# PowerBoard.net
KiCad netlist of a schematic drawn in Altium Designer
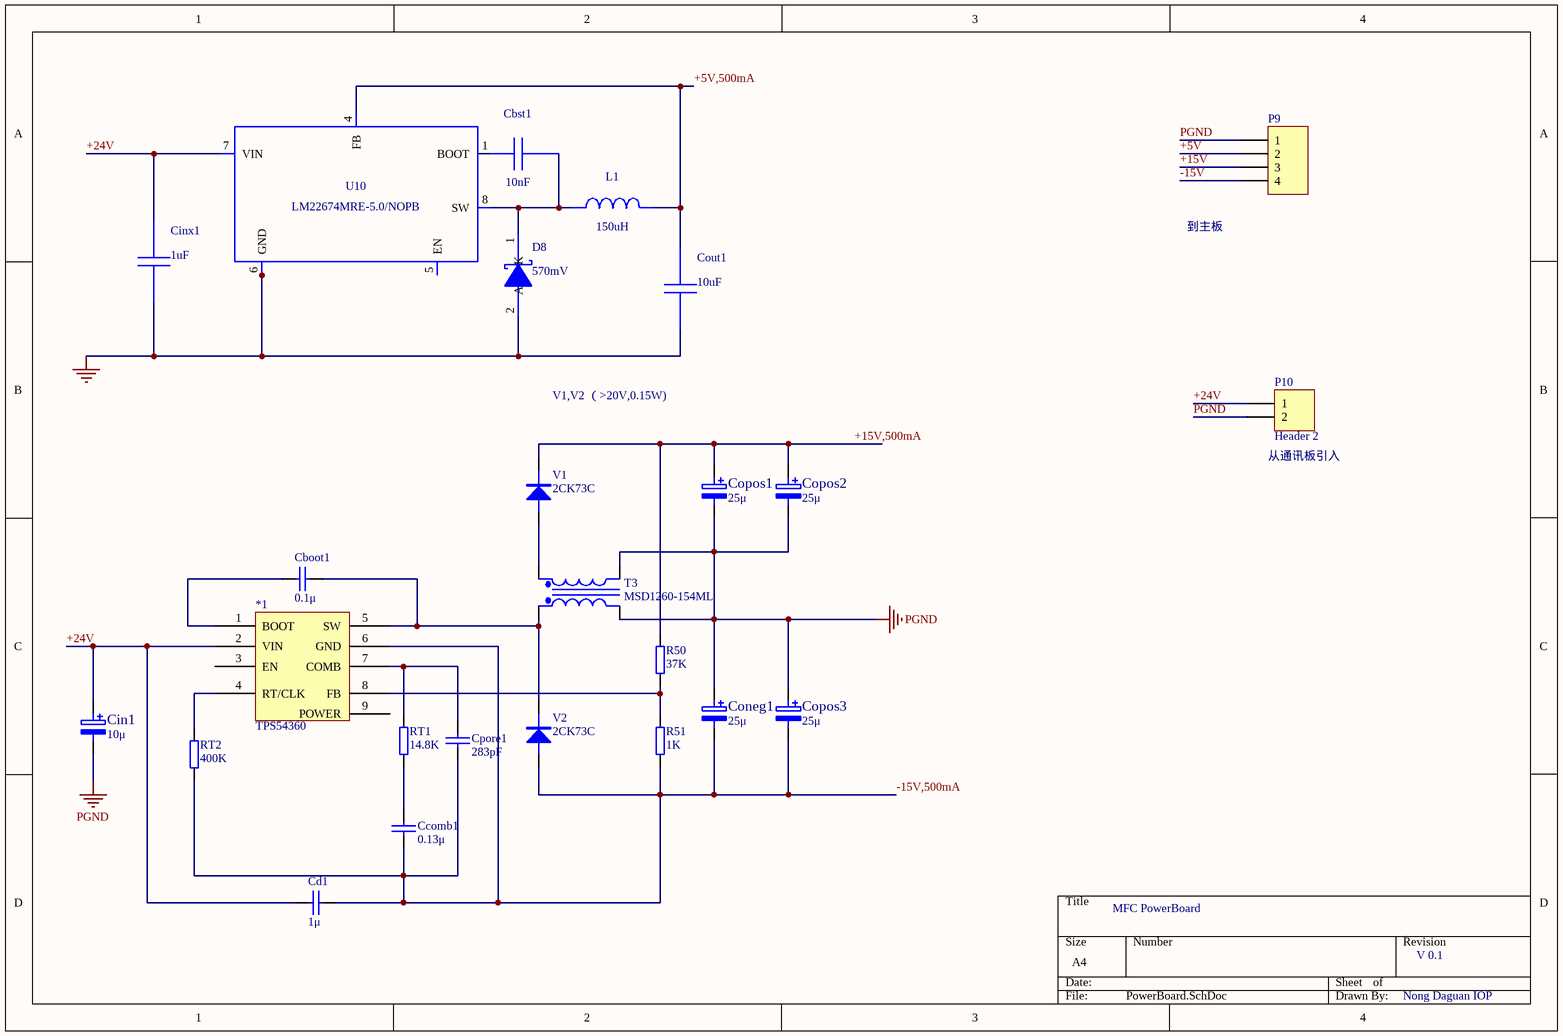
[diagram p0: PowerBoard.SchDoc]

(export (version "E")
  (design (tool "Eeschema 10.0.6"))
  (components
    (comp (ref "*1") (value "TPS54360") (libsource (lib "1.60") (part "TPS54360")))
    (comp (ref "Cboot1") (value "0.1μ") (footprint "C.1") (libsource (lib "1.60") (part "CAP")))
    (comp (ref "Cbst1")
      (value "10nF")
      (description "C0805C103K5RACTU")
      (libsource (lib "TI WEBENCH") (part "Cbst"))
    )
    (comp (ref "Ccomb1") (value "0.13μ") (footprint "C.1") (libsource (lib "1.60") (part "CAP")))
    (comp (ref "Cd1") (value "1μ") (footprint "C.1") (libsource (lib "1.60") (part "CAP")))
    (comp (ref "Cin1") (value "10μ") (footprint "CA-22U") (libsource (lib "1.60") (part "ELECTRO2")))
    (comp (ref "Cinx1")
      (value "1uF")
      (description "C1608X5R1H105K08")
      (fields (field (name "MANUFACTURER PART NUMBER") "C1608X5R1H105K080AB"))
      (libsource (lib "TI WEBENCH") (part "Cinx"))
    )
    (comp (ref "Coneg1") (value "25μ") (footprint "CA-22U") (libsource (lib "1.60") (part "ELECTRO2")))
    (comp (ref "Copos1") (value "25μ") (footprint "CA-22U") (libsource (lib "1.60") (part "ELECTRO2")))
    (comp (ref "Copos2") (value "25μ") (footprint "CA-22U") (libsource (lib "1.60") (part "ELECTRO2")))
    (comp (ref "Copos3") (value "25μ") (footprint "CA-22U") (libsource (lib "1.60") (part "ELECTRO2")))
    (comp (ref "Cout1")
      (value "10uF")
      (description "C0805C106K8PACTU")
      (libsource (lib "TI WEBENCH") (part "Cout"))
    )
    (comp (ref "Cpore1") (value "283pF") (footprint "C.1") (libsource (lib "1.60") (part "CAP")))
    (comp (ref "D8")
      (value "570mV")
      (description "PMEG6010CEH,115")
      (libsource (lib "TI WEBENCH") (part "D1"))
    )
    (comp (ref "L1")
      (value "150uH")
      (description "Unknown")
      (fields (field (name "MANUFACTURER PART NUMBER") "VLP8040T-151M"))
      (libsource (lib "TI WEBENCH") (part "L1"))
    )
    (comp (ref "P9")
      (value "~")
      (footprint "HDR1X4")
      (description "Header, 4-Pin")
      (fields (field (name "PUBLISHER") "Altium Limited"))
      (libsource (lib "Miscellaneous Connectors") (part "Header 4"))
    )
    (comp (ref "P10")
      (value "Header 2")
      (footprint "HDR1X2")
      (description "Header, 2-Pin")
      (fields (field (name "PUBLISHER") "Altium Limited"))
      (libsource (lib "Miscellaneous Connectors") (part "Header 2"))
    )
    (comp (ref "R50") (value "37K") (footprint "R.4") (libsource (lib "1.60") (part "RES_1")))
    (comp (ref "R51") (value "1K") (footprint "R.4") (libsource (lib "1.60") (part "RES_1")))
    (comp (ref "RT1") (value "14.8K") (footprint "R.4") (libsource (lib "1.60") (part "RES_1")))
    (comp (ref "RT2") (value "400K") (footprint "R.4") (libsource (lib "1.60") (part "RES_1")))
    (comp (ref "T3")
      (value "MSD1260-154ML")
      (footprint "TRF_4")
      (description "Transformer (Coupled Inductor Model)")
      (fields (field (name "PUBLISHER") "Altium Limited"))
      (libsource (lib "Miscellaneous Devices") (part "Trans Cupl"))
    )
    (comp (ref "U10")
      (value "LM22674MRE-5.0/NOPB")
      (description "LM22674MRE-5.0/N")
      (fields (field (name "PACKAGEREFERENCE") "LM22674MRE-5.0/NOPB"))
      (libsource (lib "TI WEBENCH") (part "U1"))
    )
    (comp (ref "V1") (value "2CK73C") (footprint "V.4") (libsource (lib "1.60") (part "DIODE")))
    (comp (ref "V2") (value "2CK73C") (footprint "V.4") (libsource (lib "1.60") (part "DIODE")))
  )
  (nets
    (net (code "1") (name "/+5V") (class "Default")
      (node (ref "P9") (pin "2") (pinfunction "2_2") (pintype "passive"))
    )
    (net (code "2") (name "/+5V,500mA") (class "Default")
      (node (ref "Cout1") (pin "1") (pinfunction "1_1") (pintype "passive"))
      (node (ref "L1") (pin "2") (pinfunction "2_2") (pintype "passive"))
      (node (ref "U10") (pin "4") (pinfunction "FB_4") (pintype "passive"))
    )
    (net (code "3") (name "/+15V") (class "Default")
      (node (ref "P9") (pin "3") (pinfunction "3_3") (pintype "passive"))
    )
    (net (code "4") (name "/+15V,500mA") (class "Default")
      (node (ref "Copos1") (pin "1") (pintype "passive"))
      (node (ref "Copos2") (pin "1") (pintype "passive"))
      (node (ref "R50") (pin "2") (pintype "passive"))
      (node (ref "V1") (pin "K") (pintype "passive"))
    )
    (net (code "5") (name "/+24V") (class "Default")
      (node (ref "*1") (pin "2") (pinfunction "VIN_2") (pintype "passive"))
      (node (ref "Cd1") (pin "1") (pintype "passive"))
      (node (ref "Cin1") (pin "1") (pintype "passive"))
      (node (ref "Cinx1") (pin "1") (pinfunction "1_1") (pintype "passive"))
      (node (ref "P10") (pin "1") (pinfunction "1_1") (pintype "passive"))
      (node (ref "U10") (pin "7") (pinfunction "VIN_7") (pintype "passive"))
    )
    (net (code "6") (name "/-15V") (class "Default")
      (node (ref "P9") (pin "4") (pinfunction "4_4") (pintype "passive"))
    )
    (net (code "7") (name "/-15V,500mA") (class "Default")
      (node (ref "*1") (pin "6") (pinfunction "GND_6") (pintype "passive"))
      (node (ref "Ccomb1") (pin "2") (pintype "passive"))
      (node (ref "Cd1") (pin "2") (pintype "passive"))
      (node (ref "Coneg1") (pin "2") (pintype "passive"))
      (node (ref "Copos3") (pin "2") (pintype "passive"))
      (node (ref "Cpore1") (pin "2") (pintype "passive"))
      (node (ref "R51") (pin "1") (pintype "passive"))
      (node (ref "RT2") (pin "2") (pintype "passive"))
      (node (ref "V2") (pin "A") (pintype "passive"))
    )
    (net (code "8") (name "Net-(*1-BOOT)") (class "Default")
      (node (ref "*1") (pin "1") (pinfunction "BOOT_1") (pintype "passive"))
      (node (ref "Cboot1") (pin "1") (pintype "passive"))
    )
    (net (code "9") (name "Net-(*1-COMB)") (class "Default")
      (node (ref "*1") (pin "7") (pinfunction "COMB_7") (pintype "passive"))
      (node (ref "Cpore1") (pin "1") (pintype "passive"))
      (node (ref "RT1") (pin "1") (pintype "passive"))
    )
    (net (code "10") (name "Net-(*1-FB)") (class "Default")
      (node (ref "*1") (pin "8") (pinfunction "FB_8") (pintype "passive"))
      (node (ref "R50") (pin "1") (pintype "passive"))
      (node (ref "R51") (pin "2") (pintype "passive"))
    )
    (net (code "11") (name "Net-(*1-RT{slash}CLK)") (class "Default")
      (node (ref "*1") (pin "4") (pinfunction "RT/CLK_4") (pintype "passive"))
      (node (ref "RT2") (pin "1") (pintype "passive"))
    )
    (net (code "12") (name "Net-(*1-SW)") (class "Default")
      (node (ref "*1") (pin "5") (pinfunction "SW_5") (pintype "passive"))
      (node (ref "Cboot1") (pin "2") (pintype "passive"))
      (node (ref "T3") (pin "1") (pinfunction "Pri+_1") (pintype "passive"))
      (node (ref "V2") (pin "K") (pintype "passive"))
    )
    (net (code "13") (name "Net-(Ccomb1-Pad1)") (class "Default")
      (node (ref "Ccomb1") (pin "1") (pintype "passive"))
      (node (ref "RT1") (pin "2") (pintype "passive"))
    )
    (net (code "14") (name "Net-(D8-K)") (class "Default")
      (node (ref "Cbst1") (pin "1") (pinfunction "1_1") (pintype "passive"))
      (node (ref "D8") (pin "1") (pinfunction "K_1") (pintype "passive"))
      (node (ref "L1") (pin "1") (pinfunction "1_1") (pintype "passive"))
      (node (ref "U10") (pin "8") (pinfunction "SW_8") (pintype "passive"))
    )
    (net (code "15") (name "Net-(T3-Sec+)") (class "Default")
      (node (ref "T3") (pin "3") (pinfunction "Sec+_3") (pintype "passive"))
      (node (ref "V1") (pin "A") (pintype "passive"))
    )
    (net (code "16") (name "Net-(U10-BOOT)") (class "Default")
      (node (ref "Cbst1") (pin "2") (pinfunction "2_2") (pintype "passive"))
      (node (ref "U10") (pin "1") (pinfunction "BOOT_1") (pintype "passive"))
    )
    (net (code "17") (name "PGND") (class "Default")
      (node (ref "Cin1") (pin "2") (pintype "passive"))
      (node (ref "Cinx1") (pin "2") (pinfunction "2_2") (pintype "passive"))
      (node (ref "Coneg1") (pin "1") (pintype "passive"))
      (node (ref "Copos1") (pin "2") (pintype "passive"))
      (node (ref "Copos2") (pin "2") (pintype "passive"))
      (node (ref "Copos3") (pin "1") (pintype "passive"))
      (node (ref "Cout1") (pin "2") (pinfunction "2_2") (pintype "passive"))
      (node (ref "D8") (pin "2") (pinfunction "A_2") (pintype "passive"))
      (node (ref "P10") (pin "2") (pinfunction "2_2") (pintype "passive"))
      (node (ref "P9") (pin "1") (pinfunction "1_1") (pintype "passive"))
      (node (ref "T3") (pin "2") (pinfunction "Pri-_2") (pintype "passive"))
      (node (ref "T3") (pin "4") (pinfunction "Sec-_4") (pintype "passive"))
      (node (ref "U10") (pin "2") (pinfunction "NC_2") (pintype "passive"))
      (node (ref "U10") (pin "3") (pinfunction "NC_3") (pintype "passive"))
      (node (ref "U10") (pin "6") (pinfunction "GND_6") (pintype "passive"))
      (node (ref "U10") (pin "9") (pinfunction "DAP_9") (pintype "passive"))
    )
    (net (code "18") (name "unconnected-(*1-EN-Pad3)") (class "Default")
      (node (ref "*1") (pin "3") (pinfunction "EN_3") (pintype "passive"))
    )
    (net (code "19") (name "unconnected-(*1-POWER-Pad9)") (class "Default")
      (node (ref "*1") (pin "9") (pinfunction "POWER_9") (pintype "passive"))
    )
    (net (code "20") (name "unconnected-(U10-EN-Pad5)") (class "Default")
      (node (ref "U10") (pin "5") (pinfunction "EN_5") (pintype "passive"))
    )
  )
)
